# watering.net
KiCad netlist of a schematic drawn in EAGLE
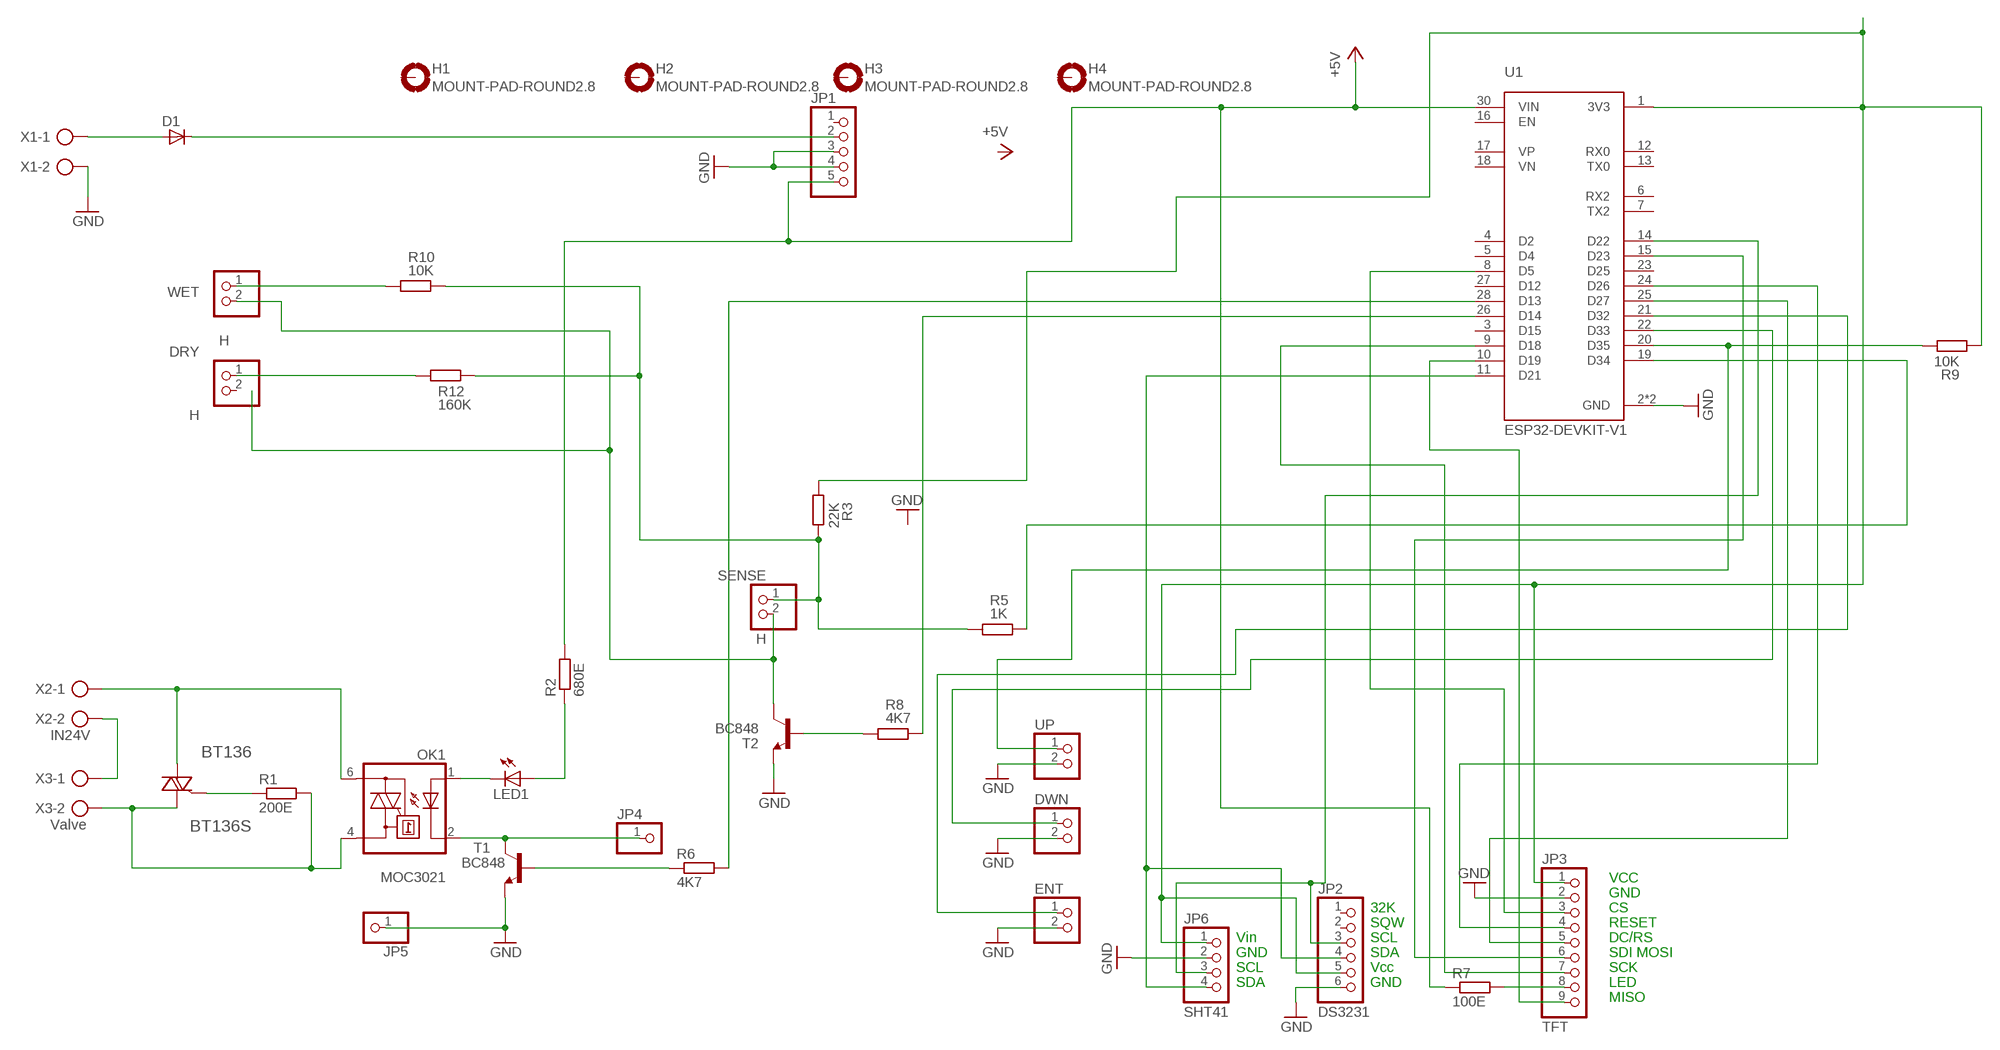
[diagram p0: schematic, sheet 1]

(export (version "E")
  (design (tool "Eeschema 10.0.6"))
  (components
    (comp (ref "BT136")
      (value "BT136S")
      (footprint "eagle-import:DPAK228P987X240-3N")
      (fields (field (name "MF") "STMicroelectronics") (field (name "MP") "T435-600B"))
      (libsource (lib "eagle-import") (part "T435-600B"))
    )
    (comp (ref "D1")
      (value "D-SOD-80")
      (footprint "eagle-import:SOD80")
      (libsource (lib "eagle-import") (part "D-SOD-80"))
    )
    (comp (ref "DRY")
      (value "H")
      (footprint "eagle-import:1X02")
      (libsource (lib "eagle-import") (part "PINHD-1X2"))
    )
    (comp (ref "DWN")
      (value "PINHD-1X2")
      (footprint "eagle-import:1X02")
      (libsource (lib "eagle-import") (part "PINHD-1X2"))
    )
    (comp (ref "ENT")
      (value "PINHD-1X2")
      (footprint "eagle-import:1X02")
      (libsource (lib "eagle-import") (part "PINHD-1X2"))
    )
    (comp (ref "H1")
      (value "MOUNT-PAD-ROUND2.8")
      (footprint "eagle-import:2,8-PAD")
      (libsource (lib "eagle-import") (part "MOUNT-PAD-ROUND2.8"))
    )
    (comp (ref "H2")
      (value "MOUNT-PAD-ROUND2.8")
      (footprint "eagle-import:2,8-PAD")
      (libsource (lib "eagle-import") (part "MOUNT-PAD-ROUND2.8"))
    )
    (comp (ref "H3")
      (value "MOUNT-PAD-ROUND2.8")
      (footprint "eagle-import:2,8-PAD")
      (libsource (lib "eagle-import") (part "MOUNT-PAD-ROUND2.8"))
    )
    (comp (ref "H4")
      (value "MOUNT-PAD-ROUND2.8")
      (footprint "eagle-import:2,8-PAD")
      (libsource (lib "eagle-import") (part "MOUNT-PAD-ROUND2.8"))
    )
    (comp (ref "JP1")
      (value "PINHD-1X5")
      (footprint "eagle-import:1X05")
      (libsource (lib "eagle-import") (part "PINHD-1X5"))
    )
    (comp (ref "JP2")
      (value "DS3231")
      (footprint "eagle-import:1X06")
      (libsource (lib "eagle-import") (part "PINHD-1X6"))
    )
    (comp (ref "JP3")
      (value "TFT")
      (footprint "eagle-import:1X09")
      (libsource (lib "eagle-import") (part "PINHD-1X9"))
    )
    (comp (ref "JP4")
      (value "PINHD-1X1")
      (footprint "eagle-import:1X01")
      (libsource (lib "eagle-import") (part "PINHD-1X1"))
    )
    (comp (ref "JP5")
      (value "PINHD-1X1")
      (footprint "eagle-import:1X01")
      (libsource (lib "eagle-import") (part "PINHD-1X1"))
    )
    (comp (ref "JP6")
      (value "SHT41")
      (footprint "eagle-import:1X04")
      (libsource (lib "eagle-import") (part "PINHD-1X4"))
    )
    (comp (ref "LED1")
      (value "LEDCHIPLED_0805")
      (footprint "eagle-import:CHIPLED_0805")
      (libsource (lib "eagle-import") (part "LEDCHIPLED_0805"))
    )
    (comp (ref "OK1")
      (value "MOC3021")
      (footprint "eagle-import:DIL6-SMD")
      (fields (field (name "MF") "FAIRCHILD SEMICONDUCTOR") (field (name "MPN") "MOC3031SM"))
      (libsource (lib "eagle-import") (part "MOC30S31"))
    )
    (comp (ref "R1")
      (value "200E")
      (footprint "eagle-import:R0603")
      (libsource (lib "eagle-import") (part "R-EU_R0603"))
    )
    (comp (ref "R2")
      (value "680E")
      (footprint "eagle-import:R0603")
      (libsource (lib "eagle-import") (part "R-EU_R0603"))
    )
    (comp (ref "R3")
      (value "22K")
      (footprint "eagle-import:R0603")
      (libsource (lib "eagle-import") (part "R-EU_R0603"))
    )
    (comp (ref "R5")
      (value "1K")
      (footprint "eagle-import:R0603")
      (libsource (lib "eagle-import") (part "R-EU_R0603"))
    )
    (comp (ref "R6")
      (value "4K7")
      (footprint "eagle-import:R0603")
      (libsource (lib "eagle-import") (part "R-EU_R0603"))
    )
    (comp (ref "R7")
      (value "100E")
      (footprint "eagle-import:R0603")
      (libsource (lib "eagle-import") (part "R-EU_R0603"))
    )
    (comp (ref "R8")
      (value "4K7")
      (footprint "eagle-import:R0603")
      (libsource (lib "eagle-import") (part "R-EU_R0603"))
    )
    (comp (ref "R9")
      (value "10K")
      (footprint "eagle-import:R0603")
      (libsource (lib "eagle-import") (part "R-EU_R0603"))
    )
    (comp (ref "R10")
      (value "10K")
      (footprint "eagle-import:R0603")
      (libsource (lib "eagle-import") (part "R-EU_R0603"))
    )
    (comp (ref "R12")
      (value "160K")
      (footprint "eagle-import:R0603")
      (libsource (lib "eagle-import") (part "R-EU_R0603"))
    )
    (comp (ref "SENSE")
      (value "H")
      (footprint "eagle-import:1X02")
      (libsource (lib "eagle-import") (part "PINHD-1X2"))
    )
    (comp (ref "T1")
      (value "BC848")
      (footprint "eagle-import:SOT23")
      (libsource (lib "eagle-import") (part "BC848"))
    )
    (comp (ref "T2")
      (value "BC848")
      (footprint "eagle-import:SOT23")
      (libsource (lib "eagle-import") (part "BC848"))
    )
    (comp (ref "U1")
      (value "ESP32-DEVKIT-V1")
      (footprint "eagle-import:MODULE_ESP32_DEVKIT_V1")
      (fields (field (name "MF") "Do it"))
      (libsource (lib "eagle-import") (part "ESP32-DEVKIT-V1"))
    )
    (comp (ref "UP")
      (value "PINHD-1X2")
      (footprint "eagle-import:1X02")
      (libsource (lib "eagle-import") (part "PINHD-1X2"))
    )
    (comp (ref "WET")
      (value "H")
      (footprint "eagle-import:1X02")
      (libsource (lib "eagle-import") (part "PINHD-1X2"))
    )
    (comp (ref "X1")
      (value "AK300/2")
      (footprint "eagle-import:AK300_2")
      (libsource (lib "eagle-import") (part "AK300/2"))
    )
    (comp (ref "X2")
      (value "IN24V")
      (footprint "eagle-import:AK300_2")
      (libsource (lib "eagle-import") (part "AK300/2"))
    )
    (comp (ref "X3")
      (value "Valve")
      (footprint "eagle-import:AK300_2")
      (libsource (lib "eagle-import") (part "AK300/2"))
    )
  )
  (nets
    (net (code "1") (name "+5V") (class "Default")
      (node (ref "JP1") (pin "5") (pinfunction "5_5") (pintype "passive"))
      (node (ref "R2") (pin "2") (pinfunction "2_2") (pintype "passive"))
      (node (ref "R7") (pin "1") (pinfunction "1_1") (pintype "passive"))
      (node (ref "U1") (pin "30") (pinfunction "VIN_30") (pintype "input"))
    )
    (net (code "2") (name "GND") (class "Default")
      (node (ref "DWN") (pin "2") (pinfunction "2_2") (pintype "passive"))
      (node (ref "ENT") (pin "2") (pinfunction "2_2") (pintype "passive"))
      (node (ref "JP1") (pin "3") (pinfunction "3_3") (pintype "passive"))
      (node (ref "JP1") (pin "4") (pinfunction "4_4") (pintype "passive"))
      (node (ref "JP2") (pin "6") (pinfunction "6_6") (pintype "passive"))
      (node (ref "JP3") (pin "2") (pinfunction "2_2") (pintype "passive"))
      (node (ref "JP5") (pin "1") (pinfunction "1_1") (pintype "passive"))
      (node (ref "JP6") (pin "2") (pinfunction "2_2") (pintype "passive"))
      (node (ref "T1") (pin "2") (pinfunction "E_2") (pintype "passive"))
      (node (ref "T2") (pin "2") (pinfunction "E_2") (pintype "passive"))
      (node (ref "U1") (pin "2") (pinfunction "GND_2") (pintype "power_in"))
      (node (ref "U1") (pin "29") (pinfunction "GND_29") (pintype "power_in"))
      (node (ref "UP") (pin "2") (pinfunction "2_2") (pintype "passive"))
      (node (ref "X1") (pin "2") (pinfunction "KL_2") (pintype "passive"))
    )
    (net (code "3") (name "Net-(BT136-A1)") (class "Default")
      (node (ref "BT136") (pin "1") (pinfunction "A1_1") (pintype "passive"))
      (node (ref "OK1") (pin "4") (pinfunction "A1_4") (pintype "passive"))
      (node (ref "R1") (pin "2") (pinfunction "2_2") (pintype "passive"))
      (node (ref "X3") (pin "2") (pinfunction "KL_2") (pintype "passive"))
    )
    (net (code "4") (name "Net-(BT136-A2)") (class "Default")
      (node (ref "BT136") (pin "3") (pinfunction "A2_3") (pintype "passive"))
      (node (ref "OK1") (pin "6") (pinfunction "A2_6") (pintype "passive"))
      (node (ref "X2") (pin "1") (pinfunction "KL_1") (pintype "passive"))
    )
    (net (code "5") (name "Net-(BT136-G)") (class "Default")
      (node (ref "BT136") (pin "2") (pinfunction "G_2") (pintype "passive"))
      (node (ref "R1") (pin "1") (pinfunction "1_1") (pintype "passive"))
    )
    (net (code "6") (name "Net-(D1-A)") (class "Default")
      (node (ref "D1") (pin "2") (pinfunction "A_2") (pintype "passive"))
      (node (ref "X1") (pin "1") (pinfunction "KL_1") (pintype "passive"))
    )
    (net (code "7") (name "Net-(D1-C)") (class "Default")
      (node (ref "D1") (pin "1") (pinfunction "C_1") (pintype "passive"))
      (node (ref "JP1") (pin "2") (pinfunction "2_2") (pintype "passive"))
    )
    (net (code "8") (name "Net-(DRY-Pad1)") (class "Default")
      (node (ref "DRY") (pin "1") (pinfunction "1_1") (pintype "passive"))
      (node (ref "R12") (pin "1") (pinfunction "1_1") (pintype "passive"))
    )
    (net (code "9") (name "Net-(JP3-Pad8)") (class "Default")
      (node (ref "JP3") (pin "8") (pinfunction "8_8") (pintype "passive"))
      (node (ref "R7") (pin "2") (pinfunction "2_2") (pintype "passive"))
    )
    (net (code "10") (name "Net-(LED1-PadA)") (class "Default")
      (node (ref "LED1") (pin "A") (pinfunction "A_A") (pintype "passive"))
      (node (ref "R2") (pin "1") (pinfunction "1_1") (pintype "passive"))
    )
    (net (code "11") (name "Net-(OK1-A)") (class "Default")
      (node (ref "LED1") (pin "C") (pinfunction "C_C") (pintype "passive"))
      (node (ref "OK1") (pin "1") (pinfunction "A_1") (pintype "passive"))
    )
    (net (code "12") (name "Net-(OK1-C)") (class "Default")
      (node (ref "JP4") (pin "1") (pinfunction "1_1") (pintype "passive"))
      (node (ref "OK1") (pin "2") (pinfunction "C_2") (pintype "passive"))
      (node (ref "T1") (pin "3") (pinfunction "C_3") (pintype "passive"))
    )
    (net (code "13") (name "Net-(R10-Pad1)") (class "Default")
      (node (ref "R10") (pin "1") (pinfunction "1_1") (pintype "passive"))
      (node (ref "WET") (pin "1") (pinfunction "1_1") (pintype "passive"))
    )
    (net (code "14") (name "Net-(R10-Pad2)") (class "Default")
      (node (ref "R10") (pin "2") (pinfunction "2_2") (pintype "passive"))
      (node (ref "R12") (pin "2") (pinfunction "2_2") (pintype "passive"))
      (node (ref "R3") (pin "2") (pinfunction "2_2") (pintype "passive"))
      (node (ref "R5") (pin "1") (pinfunction "1_1") (pintype "passive"))
      (node (ref "SENSE") (pin "1") (pinfunction "1_1") (pintype "passive"))
    )
    (net (code "15") (name "Net-(T1-B)") (class "Default")
      (node (ref "R6") (pin "1") (pinfunction "1_1") (pintype "passive"))
      (node (ref "T1") (pin "1") (pinfunction "B_1") (pintype "passive"))
    )
    (net (code "16") (name "Net-(T2-B)") (class "Default")
      (node (ref "R8") (pin "1") (pinfunction "1_1") (pintype "passive"))
      (node (ref "T2") (pin "1") (pinfunction "B_1") (pintype "passive"))
    )
    (net (code "17") (name "Net-(T2-C)") (class "Default")
      (node (ref "SENSE") (pin "2") (pinfunction "2_2") (pintype "passive"))
      (node (ref "T2") (pin "3") (pinfunction "C_3") (pintype "passive"))
      (node (ref "WET") (pin "2") (pinfunction "2_2") (pintype "passive"))
    )
    (net (code "18") (name "Net-(U1-3V3)") (class "Default")
      (node (ref "JP2") (pin "5") (pinfunction "5_5") (pintype "passive"))
      (node (ref "JP3") (pin "1") (pinfunction "1_1") (pintype "passive"))
      (node (ref "JP6") (pin "1") (pinfunction "1_1") (pintype "passive"))
      (node (ref "R3") (pin "1") (pinfunction "1_1") (pintype "passive"))
      (node (ref "R9") (pin "1") (pinfunction "1_1") (pintype "passive"))
      (node (ref "U1") (pin "1") (pinfunction "3V3_1") (pintype "output"))
    )
    (net (code "19") (name "Net-(U1-D5)") (class "Default")
      (node (ref "JP3") (pin "3") (pinfunction "3_3") (pintype "passive"))
      (node (ref "U1") (pin "8") (pinfunction "D5_8") (pintype "bidirectional"))
    )
    (net (code "20") (name "Net-(U1-D13)") (class "Default")
      (node (ref "R6") (pin "2") (pinfunction "2_2") (pintype "passive"))
      (node (ref "U1") (pin "28") (pinfunction "D13_28") (pintype "bidirectional"))
    )
    (net (code "21") (name "Net-(U1-D14)") (class "Default")
      (node (ref "R8") (pin "2") (pinfunction "2_2") (pintype "passive"))
      (node (ref "U1") (pin "26") (pinfunction "D14_26") (pintype "bidirectional"))
    )
    (net (code "22") (name "Net-(U1-D18)") (class "Default")
      (node (ref "JP3") (pin "7") (pinfunction "7_7") (pintype "passive"))
      (node (ref "U1") (pin "9") (pinfunction "D18_9") (pintype "bidirectional"))
    )
    (net (code "23") (name "Net-(U1-D19)") (class "Default")
      (node (ref "JP3") (pin "9") (pinfunction "9_9") (pintype "passive"))
      (node (ref "U1") (pin "10") (pinfunction "D19_10") (pintype "bidirectional"))
    )
    (net (code "24") (name "Net-(U1-D21)") (class "Default")
      (node (ref "JP2") (pin "4") (pinfunction "4_4") (pintype "passive"))
      (node (ref "JP6") (pin "4") (pinfunction "4_4") (pintype "passive"))
      (node (ref "U1") (pin "11") (pinfunction "D21_11") (pintype "bidirectional"))
    )
    (net (code "25") (name "Net-(U1-D22)") (class "Default")
      (node (ref "JP2") (pin "3") (pinfunction "3_3") (pintype "passive"))
      (node (ref "JP6") (pin "3") (pinfunction "3_3") (pintype "passive"))
      (node (ref "U1") (pin "14") (pinfunction "D22_14") (pintype "bidirectional"))
    )
    (net (code "26") (name "Net-(U1-D23)") (class "Default")
      (node (ref "JP3") (pin "6") (pinfunction "6_6") (pintype "passive"))
      (node (ref "U1") (pin "15") (pinfunction "D23_15") (pintype "bidirectional"))
    )
    (net (code "27") (name "Net-(U1-D26)") (class "Default")
      (node (ref "JP3") (pin "4") (pinfunction "4_4") (pintype "passive"))
      (node (ref "U1") (pin "24") (pinfunction "D26_24") (pintype "bidirectional"))
    )
    (net (code "28") (name "Net-(U1-D27)") (class "Default")
      (node (ref "JP3") (pin "5") (pinfunction "5_5") (pintype "passive"))
      (node (ref "U1") (pin "25") (pinfunction "D27_25") (pintype "bidirectional"))
    )
    (net (code "29") (name "Net-(U1-D32)") (class "Default")
      (node (ref "ENT") (pin "1") (pinfunction "1_1") (pintype "passive"))
      (node (ref "U1") (pin "21") (pinfunction "D32_21") (pintype "bidirectional"))
    )
    (net (code "30") (name "Net-(U1-D33)") (class "Default")
      (node (ref "DWN") (pin "1") (pinfunction "1_1") (pintype "passive"))
      (node (ref "U1") (pin "22") (pinfunction "D33_22") (pintype "bidirectional"))
    )
    (net (code "31") (name "Net-(U1-D34)") (class "Default")
      (node (ref "R5") (pin "2") (pinfunction "2_2") (pintype "passive"))
      (node (ref "U1") (pin "19") (pinfunction "D34_19") (pintype "bidirectional"))
    )
    (net (code "32") (name "Net-(U1-D35)") (class "Default")
      (node (ref "R9") (pin "2") (pinfunction "2_2") (pintype "passive"))
      (node (ref "U1") (pin "20") (pinfunction "D35_20") (pintype "bidirectional"))
      (node (ref "UP") (pin "1") (pinfunction "1_1") (pintype "passive"))
    )
    (net (code "33") (name "Net-(X2B-KL)") (class "Default")
      (node (ref "X2") (pin "2") (pinfunction "KL_2") (pintype "passive"))
      (node (ref "X3") (pin "1") (pinfunction "KL_1") (pintype "passive"))
    )
    (net (code "34") (name "unconnected-(DRY-Pad2)") (class "Default")
      (node (ref "DRY") (pin "2") (pinfunction "2_2") (pintype "passive"))
    )
    (net (code "35") (name "unconnected-(H1-MOUNT-PadB2,8)") (class "Default")
      (node (ref "H1") (pin "B2,8") (pinfunction "MOUNT_B2,8") (pintype "passive"))
    )
    (net (code "36") (name "unconnected-(H2-MOUNT-PadB2,8)") (class "Default")
      (node (ref "H2") (pin "B2,8") (pinfunction "MOUNT_B2,8") (pintype "passive"))
    )
    (net (code "37") (name "unconnected-(H3-MOUNT-PadB2,8)") (class "Default")
      (node (ref "H3") (pin "B2,8") (pinfunction "MOUNT_B2,8") (pintype "passive"))
    )
    (net (code "38") (name "unconnected-(H4-MOUNT-PadB2,8)") (class "Default")
      (node (ref "H4") (pin "B2,8") (pinfunction "MOUNT_B2,8") (pintype "passive"))
    )
    (net (code "39") (name "unconnected-(JP1-Pad1)") (class "Default")
      (node (ref "JP1") (pin "1") (pinfunction "1_1") (pintype "passive"))
    )
    (net (code "40") (name "unconnected-(JP2-Pad1)") (class "Default")
      (node (ref "JP2") (pin "1") (pinfunction "1_1") (pintype "passive"))
    )
    (net (code "41") (name "unconnected-(JP2-Pad2)") (class "Default")
      (node (ref "JP2") (pin "2") (pinfunction "2_2") (pintype "passive"))
    )
    (net (code "42") (name "unconnected-(U1-D2-Pad4)") (class "Default")
      (node (ref "U1") (pin "4") (pinfunction "D2_4") (pintype "bidirectional"))
    )
    (net (code "43") (name "unconnected-(U1-D4-Pad5)") (class "Default")
      (node (ref "U1") (pin "5") (pinfunction "D4_5") (pintype "bidirectional"))
    )
    (net (code "44") (name "unconnected-(U1-D12-Pad27)") (class "Default")
      (node (ref "U1") (pin "27") (pinfunction "D12_27") (pintype "bidirectional"))
    )
    (net (code "45") (name "unconnected-(U1-D15-Pad3)") (class "Default")
      (node (ref "U1") (pin "3") (pinfunction "D15_3") (pintype "bidirectional"))
    )
    (net (code "46") (name "unconnected-(U1-D25-Pad23)") (class "Default")
      (node (ref "U1") (pin "23") (pinfunction "D25_23") (pintype "bidirectional"))
    )
    (net (code "47") (name "unconnected-(U1-EN-Pad16)") (class "Default")
      (node (ref "U1") (pin "16") (pinfunction "EN_16") (pintype "input"))
    )
    (net (code "48") (name "unconnected-(U1-RX0-Pad12)") (class "Default")
      (node (ref "U1") (pin "12") (pinfunction "RX0_12") (pintype "input"))
    )
    (net (code "49") (name "unconnected-(U1-RX2-Pad6)") (class "Default")
      (node (ref "U1") (pin "6") (pinfunction "RX2_6") (pintype "input"))
    )
    (net (code "50") (name "unconnected-(U1-TX0-Pad13)") (class "Default")
      (node (ref "U1") (pin "13") (pinfunction "TX0_13") (pintype "output"))
    )
    (net (code "51") (name "unconnected-(U1-TX2-Pad7)") (class "Default")
      (node (ref "U1") (pin "7") (pinfunction "TX2_7") (pintype "output"))
    )
    (net (code "52") (name "unconnected-(U1-VN-Pad18)") (class "Default")
      (node (ref "U1") (pin "18") (pinfunction "VN_18") (pintype "bidirectional"))
    )
    (net (code "53") (name "unconnected-(U1-VP-Pad17)") (class "Default")
      (node (ref "U1") (pin "17") (pinfunction "VP_17") (pintype "bidirectional"))
    )
  )
)
